# BOTONES.net
KiCad netlist of a schematic drawn in Altium Designer
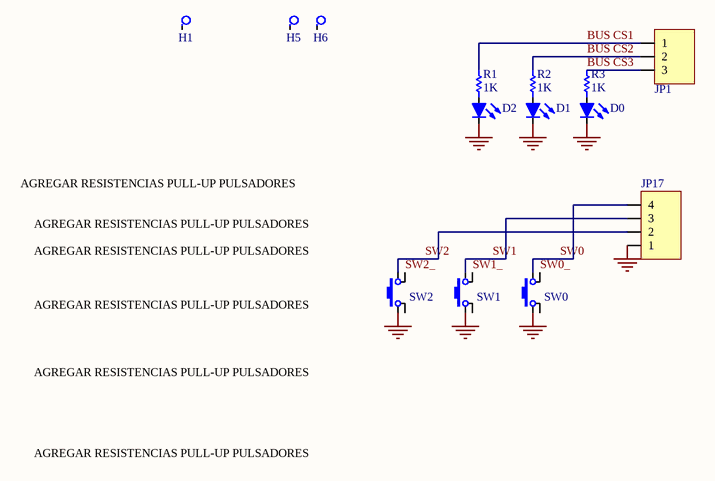
[diagram p0: BOTONES.SchDoc]

(export (version "E")
  (design (tool "Eeschema 10.0.6"))
  (components
    (comp (ref "D0")
      (value "Led 5mm Rojo Difuso")
      (footprint "LED5mm ROJO")
      (libsource (lib "FEDE") (part "Led 5mm Rojo Difuso"))
    )
    (comp (ref "D1")
      (value "Led 5mm Rojo Difuso")
      (footprint "LED5mm ROJO")
      (libsource (lib "FEDE") (part "Led 5mm Rojo Difuso"))
    )
    (comp (ref "D2")
      (value "Led 5mm Rojo Difuso")
      (footprint "LED5mm ROJO")
      (libsource (lib "FEDE") (part "Led 5mm Rojo Difuso"))
    )
    (comp (ref "H1")
      (value "Agujero de Montaje")
      (footprint "agujero")
      (libsource (lib "FEDE") (part "Agujero de Montaje"))
    )
    (comp (ref "H5")
      (value "Agujero de Montaje")
      (footprint "agujero")
      (libsource (lib "FEDE") (part "Agujero de Montaje"))
    )
    (comp (ref "H6")
      (value "Agujero de Montaje")
      (footprint "agujero")
      (libsource (lib "FEDE") (part "Agujero de Montaje"))
    )
    (comp (ref "JP1")
      (value "Header3x1")
      (footprint "CONPOL3X1_90")
      (description "Header 3x1")
      (libsource (lib "FEDE") (part "Header3x1"))
    )
    (comp (ref "JP17")
      (value "Header4x1")
      (footprint "CONPOL4x1_90")
      (description "Header 4x1")
      (libsource (lib "FEDE") (part "Header4x1"))
    )
    (comp (ref "R1")
      (value "1K")
      (footprint "1206NP")
      (description "Resistor")
      (fields (field (name "POWER") "0.25W") (field (name "Comment") "Res"))
      (libsource (lib "FEDE") (part "Res"))
    )
    (comp (ref "R2")
      (value "1K")
      (footprint "1206NP")
      (description "Resistor")
      (fields (field (name "POWER") "0.25W") (field (name "Comment") "Res"))
      (libsource (lib "FEDE") (part "Res"))
    )
    (comp (ref "R3")
      (value "1K")
      (footprint "1206NP")
      (description "Resistor")
      (fields (field (name "POWER") "0.25W") (field (name "Comment") "Res"))
      (libsource (lib "FEDE") (part "Res"))
    )
    (comp (ref "SW0") (value "SW_T_5MM") (footprint "SW_T_5MM") (libsource (lib "FEDE") (part "SW_T_5MM")))
    (comp (ref "SW1") (value "SW_T_5MM") (footprint "SW_T_5MM") (libsource (lib "FEDE") (part "SW_T_5MM")))
    (comp (ref "SW2") (value "SW_T_5MM") (footprint "SW_T_5MM") (libsource (lib "FEDE") (part "SW_T_5MM")))
  )
  (nets
    (net (code "1") (name "/BUS CS1") (class "Default")
      (node (ref "JP1") (pin "1") (pinfunction "1_1") (pintype "passive"))
      (node (ref "R1") (pin "2") (pinfunction "2_2") (pintype "passive"))
    )
    (net (code "2") (name "/BUS CS2") (class "Default")
      (node (ref "JP1") (pin "2") (pinfunction "2_2") (pintype "passive"))
      (node (ref "R2") (pin "2") (pinfunction "2_2") (pintype "passive"))
    )
    (net (code "3") (name "/BUS CS3") (class "Default")
      (node (ref "JP1") (pin "3") (pinfunction "3_3") (pintype "passive"))
      (node (ref "R3") (pin "2") (pinfunction "2_2") (pintype "passive"))
    )
    (net (code "4") (name "/SW0") (class "Default")
      (node (ref "JP17") (pin "4") (pinfunction "4_4") (pintype "passive"))
      (node (ref "SW0") (pin "4") (pinfunction "4_4") (pintype "passive"))
    )
    (net (code "5") (name "/SW0_") (class "Default")
      (node (ref "SW0") (pin "2") (pinfunction "2_2") (pintype "passive"))
    )
    (net (code "6") (name "/SW1") (class "Default")
      (node (ref "JP17") (pin "3") (pinfunction "3_3") (pintype "passive"))
      (node (ref "SW1") (pin "4") (pinfunction "4_4") (pintype "passive"))
    )
    (net (code "7") (name "/SW1_") (class "Default")
      (node (ref "SW1") (pin "2") (pinfunction "2_2") (pintype "passive"))
    )
    (net (code "8") (name "/SW2") (class "Default")
      (node (ref "JP17") (pin "2") (pinfunction "2_2") (pintype "passive"))
      (node (ref "SW2") (pin "4") (pinfunction "4_4") (pintype "passive"))
    )
    (net (code "9") (name "/SW2_") (class "Default")
      (node (ref "SW2") (pin "2") (pinfunction "2_2") (pintype "passive"))
    )
    (net (code "10") (name "GND") (class "Default")
      (node (ref "D0") (pin "2") (pinfunction "K_2") (pintype "passive"))
      (node (ref "D1") (pin "2") (pinfunction "K_2") (pintype "passive"))
      (node (ref "D2") (pin "2") (pinfunction "K_2") (pintype "passive"))
      (node (ref "JP17") (pin "1") (pinfunction "1_1") (pintype "passive"))
      (node (ref "SW0") (pin "3") (pinfunction "3_3") (pintype "passive"))
      (node (ref "SW1") (pin "3") (pinfunction "3_3") (pintype "passive"))
      (node (ref "SW2") (pin "3") (pinfunction "3_3") (pintype "passive"))
    )
    (net (code "11") (name "Net-(D0-A)") (class "Default")
      (node (ref "D0") (pin "1") (pinfunction "A_1") (pintype "passive"))
      (node (ref "R3") (pin "1") (pinfunction "1_1") (pintype "passive"))
    )
    (net (code "12") (name "Net-(D1-A)") (class "Default")
      (node (ref "D1") (pin "1") (pinfunction "A_1") (pintype "passive"))
      (node (ref "R2") (pin "1") (pinfunction "1_1") (pintype "passive"))
    )
    (net (code "13") (name "Net-(D2-A)") (class "Default")
      (node (ref "D2") (pin "1") (pinfunction "A_1") (pintype "passive"))
      (node (ref "R1") (pin "1") (pinfunction "1_1") (pintype "passive"))
    )
    (net (code "14") (name "unconnected-(H1-Pad1)") (class "Default")
      (node (ref "H1") (pin "1") (pinfunction "1_1") (pintype "passive"))
    )
    (net (code "15") (name "unconnected-(H5-Pad1)") (class "Default")
      (node (ref "H5") (pin "1") (pinfunction "1_1") (pintype "passive"))
    )
    (net (code "16") (name "unconnected-(H6-Pad1)") (class "Default")
      (node (ref "H6") (pin "1") (pinfunction "1_1") (pintype "passive"))
    )
    (net (code "17") (name "unconnected-(SW0-Pad1)") (class "Default")
      (node (ref "SW0") (pin "1") (pinfunction "1_1") (pintype "passive"))
    )
    (net (code "18") (name "unconnected-(SW1-Pad1)") (class "Default")
      (node (ref "SW1") (pin "1") (pinfunction "1_1") (pintype "passive"))
    )
    (net (code "19") (name "unconnected-(SW2-Pad1)") (class "Default")
      (node (ref "SW2") (pin "1") (pinfunction "1_1") (pintype "passive"))
    )
  )
)
